# TIPD156_SCH.net
KiCad netlist of a schematic drawn in Altium Designer
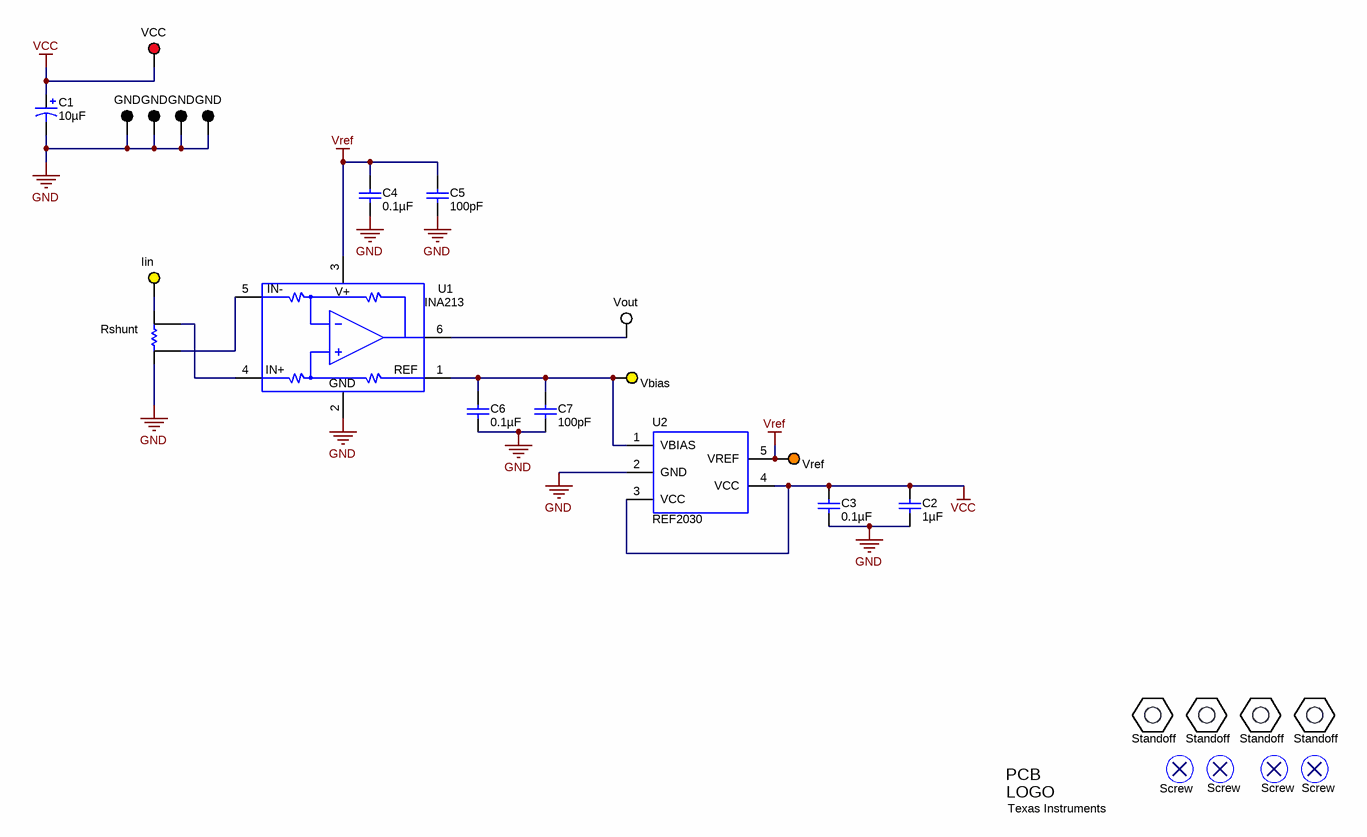
[diagram p0: TIPD156 SCH.SchDoc]

(export (version "E")
  (design (tool "Eeschema 10.0.6"))
  (components
    (comp (ref "C1")
      (value "TPSC106K025R0500")
      (footprint "6032-28")
      (description "CAP, TA, 10uF, 25V, +/-10%, 0.5 ohm, SMD")
      (fields
        (field (name "VALUEDISPLAYED") "10µF")
        (field (name "MANUFACTURER") "AVX")
        (field (name "PUBLISHER") "Texas Instruments")
      )
      (libsource (lib "Capacitor_Tantalum") (part "TPSC106K025R0500"))
    )
    (comp (ref "C2")
      (value "C1608X7R1C105K")
      (footprint "0603")
      (description "CAP, CERM, 1uF, 16V, +/-10%, X7R, 0603")
      (fields
        (field (name "VALUEDISPLAYED") "1µF")
        (field (name "MANUFACTURER") "TDK")
        (field (name "PUBLISHER") "Texas Instruments")
      )
      (libsource (lib "Capacitor_Ceramic") (part "C1608X7R1C105K"))
    )
    (comp (ref "C3")
      (value "06033C104KAT2A")
      (footprint "0603")
      (description "CAP, CERM, 0.1uF, 25V, +/-10%, X7R, 0603")
      (fields
        (field (name "VALUEDISPLAYED") "0.1µF")
        (field (name "MANUFACTURER") "AVX")
        (field (name "PUBLISHER") "Texas Instruments")
      )
      (libsource (lib "Capacitor_Ceramic") (part "06033C104KAT2A"))
    )
    (comp (ref "C4")
      (value "06033C104KAT2A")
      (footprint "0603")
      (description "CAP, CERM, 0.1uF, 25V, +/-10%, X7R, 0603")
      (fields
        (field (name "VALUEDISPLAYED") "0.1µF")
        (field (name "MANUFACTURER") "AVX")
        (field (name "PUBLISHER") "Texas Instruments")
      )
      (libsource (lib "Capacitor_Ceramic") (part "06033C104KAT2A"))
    )
    (comp (ref "C5")
      (value "06035A101JAT2A")
      (footprint "0603")
      (description "CAP, CERM, 100pF, 50V, +/-5%, C0G/NP0, 0603")
      (fields
        (field (name "VALUEDISPLAYED") "100pF")
        (field (name "MANUFACTURER") "AVX")
        (field (name "PUBLISHER") "Texas Instruments")
      )
      (libsource (lib "Capacitor_Ceramic") (part "06035A101JAT2A"))
    )
    (comp (ref "C6")
      (value "06033C104KAT2A")
      (footprint "0603")
      (description "CAP, CERM, 0.1uF, 25V, +/-10%, X7R, 0603")
      (fields
        (field (name "VALUEDISPLAYED") "0.1µF")
        (field (name "MANUFACTURER") "AVX")
        (field (name "PUBLISHER") "Texas Instruments")
      )
      (libsource (lib "Capacitor_Ceramic") (part "06033C104KAT2A"))
    )
    (comp (ref "C7")
      (value "06035A101JAT2A")
      (footprint "0603")
      (description "CAP, CERM, 100pF, 50V, +/-5%, C0G/NP0, 0603")
      (fields
        (field (name "VALUEDISPLAYED") "100pF")
        (field (name "MANUFACTURER") "AVX")
        (field (name "PUBLISHER") "Texas Instruments")
      )
      (libsource (lib "Capacitor_Ceramic") (part "06035A101JAT2A"))
    )
    (comp (ref "Logo1")
      (value "Texas Instruments")
      (footprint "TI_Symbol_Overlay_Small")
      (description "Texas Instrument Corporate Signature")
      (fields (field (name "SYMBOLCREATOR") "codlsc") (field (name "PUBLISHER") "Texas Instruments"))
      (libsource (lib "Logos") (part "TI_Logo"))
    )
    (comp (ref "Rshunt")
      (value "~")
      (footprint "myPCBlib:CSM2512")
      (description "RES, 0.010 ohm, 0.1%, 1W, CSM2512")
      (fields (field (name "PUBLISHER") "Texas Instruments"))
      (libsource (lib "mySCHlib") (part "10m ohm shunt resistor"))
    )
    (comp (ref "TP1")
      (value "Vout")
      (footprint "Keystone5007")
      (description "Test Point, Compact, White, TH")
      (fields
        (field (name "PARTNUMBER") "5007")
        (field (name "MANUFACTURER") "Keystone")
        (field (name "PUBLISHER") "Texas Instruments")
      )
      (libsource (lib "Connectors") (part "5007"))
    )
    (comp (ref "TP2")
      (value "VCC")
      (footprint "Keystone5005")
      (description "Test Point, TH, Compact, Red")
      (fields
        (field (name "MANUFACTURER") "Keystone")
        (field (name "DIGIKEYPARTNUMBER") "5005K-ND")
        (field (name "PUBLISHER") "Texas Instruments")
      )
      (libsource (lib "TemplateSCHLib") (part "5005"))
    )
    (comp (ref "TP3")
      (value "GND")
      (footprint "Keystone5006")
      (description "Test Point, TH, Compact, Black")
      (fields
        (field (name "MANUFACTURER") "Keystone")
        (field (name "DIGIKEYPARTNUMBER") "5006K-ND")
        (field (name "PUBLISHER") "Texas Instruments")
      )
      (libsource (lib "TemplateSCHLib") (part "5006"))
    )
    (comp (ref "TP4")
      (value "GND")
      (footprint "Keystone5006")
      (description "Test Point, TH, Compact, Black")
      (fields
        (field (name "MANUFACTURER") "Keystone")
        (field (name "DIGIKEYPARTNUMBER") "5006K-ND")
        (field (name "PUBLISHER") "Texas Instruments")
      )
      (libsource (lib "TemplateSCHLib") (part "5006"))
    )
    (comp (ref "TP5")
      (value "GND")
      (footprint "Keystone5006")
      (description "Test Point, TH, Compact, Black")
      (fields
        (field (name "MANUFACTURER") "Keystone")
        (field (name "DIGIKEYPARTNUMBER") "5006K-ND")
        (field (name "PUBLISHER") "Texas Instruments")
      )
      (libsource (lib "TemplateSCHLib") (part "5006"))
    )
    (comp (ref "TP6")
      (value "GND")
      (footprint "Keystone5006")
      (description "Test Point, TH, Compact, Black")
      (fields
        (field (name "MANUFACTURER") "Keystone")
        (field (name "DIGIKEYPARTNUMBER") "5006K-ND")
        (field (name "PUBLISHER") "Texas Instruments")
      )
      (libsource (lib "TemplateSCHLib") (part "5006"))
    )
    (comp (ref "TP7")
      (value "Vbias")
      (footprint "Keystone5009")
      (description "Test Point, Compact, Yellow, TH")
      (fields
        (field (name "PARTNUMBER") "5009")
        (field (name "MANUFACTURER") "Keystone")
        (field (name "PUBLISHER") "Texas Instruments")
      )
      (libsource (lib "Connectors") (part "5009"))
    )
    (comp (ref "TP8")
      (value "Vref")
      (footprint "Keystone5008")
      (description "Test Point, Compact, Orange, TH")
      (fields
        (field (name "PARTNUMBER") "5008")
        (field (name "MANUFACTURER") "Keystone")
        (field (name "PUBLISHER") "Texas Instruments")
      )
      (libsource (lib "Connectors") (part "5008"))
    )
    (comp (ref "TP9")
      (value "Iin")
      (footprint "Keystone5009")
      (description "Test Point, Compact, Yellow, TH")
      (fields
        (field (name "PARTNUMBER") "5009")
        (field (name "MANUFACTURER") "Keystone")
        (field (name "PUBLISHER") "Texas Instruments")
      )
      (libsource (lib "Connectors") (part "5009"))
    )
    (comp (ref "U1")
      (value "INA213")
      (footprint "PALinearPCBLib:SC70-6 (DCK) Low Density")
      (description "IC, Low Power, Single-Supply Differrence Amplifier")
      (fields (field (name "PARTNUMBER") "INA132U") (field (name "MANUFACTURER") "TI"))
      (libsource (lib "PALinearSCHLib") (part "INA213"))
    )
    (comp (ref "U2")
      (value "REF2030")
      (footprint "PALinearPCBLib:SOT23-5 (DBV) low density")
      (fields (field (name "MANUFACTURER") "Texas Instruments") (field (name "SYMBOLCREATOR") "Use a-id"))
      (libsource (lib "PALinearSCHLib") (part "REF2030"))
    )
    (comp (ref "U90")
      (value "Standoff")
      (footprint "STANDOFF HEX 4-40THR ALUM 1\"L")
      (description "STANDOFF HEX 4-40THR ALUM 1\"L")
      (fields
        (field (name "MANUFACTURER") "Keystone")
        (field (name "PARTNUMBER") "2205")
        (field (name "SYMBOLCREATOR") "Use LDAP id")
      )
      (libsource (lib "TemplateSCHLib") (part "Standoff, 1{dblquote}, 4-40, Alum, F-F"))
    )
    (comp (ref "U91")
      (value "Standoff")
      (footprint "STANDOFF HEX 4-40THR ALUM 1\"L")
      (description "STANDOFF HEX 4-40THR ALUM 1\"L")
      (fields
        (field (name "MANUFACTURER") "Keystone")
        (field (name "PARTNUMBER") "2205")
        (field (name "SYMBOLCREATOR") "Use LDAP id")
      )
      (libsource (lib "TemplateSCHLib") (part "Standoff, 1{dblquote}, 4-40, Alum, F-F"))
    )
    (comp (ref "U92")
      (value "Standoff")
      (footprint "STANDOFF HEX 4-40THR ALUM 1\"L")
      (description "STANDOFF HEX 4-40THR ALUM 1\"L")
      (fields
        (field (name "MANUFACTURER") "Keystone")
        (field (name "PARTNUMBER") "2205")
        (field (name "SYMBOLCREATOR") "Use LDAP id")
      )
      (libsource (lib "TemplateSCHLib") (part "Standoff, 1{dblquote}, 4-40, Alum, F-F"))
    )
    (comp (ref "U93")
      (value "Standoff")
      (footprint "STANDOFF HEX 4-40THR ALUM 1\"L")
      (description "STANDOFF HEX 4-40THR ALUM 1\"L")
      (fields
        (field (name "MANUFACTURER") "Keystone")
        (field (name "PARTNUMBER") "2205")
        (field (name "SYMBOLCREATOR") "Use LDAP id")
      )
      (libsource (lib "TemplateSCHLib") (part "Standoff, 1{dblquote}, 4-40, Alum, F-F"))
    )
    (comp (ref "U94")
      (value "Screw")
      (description "MACHINE SCREW PAN PHILLIPS 4-40")
      (fields
        (field (name "MANUFACTURER") "B&F Fastener Supply")
        (field (name "PARTNUMBER") "PMSSS 440 0025 PH")
        (field (name "SYMBOLCREATOR") "Use LDAP id")
      )
      (libsource (lib "TemplateSCHLib") (part "Machine Screw, 4-40, 0.25{dblquote}"))
    )
    (comp (ref "U95")
      (value "Screw")
      (description "MACHINE SCREW PAN PHILLIPS 4-40")
      (fields
        (field (name "MANUFACTURER") "B&F Fastener Supply")
        (field (name "PARTNUMBER") "PMSSS 440 0025 PH")
        (field (name "SYMBOLCREATOR") "Use LDAP id")
      )
      (libsource (lib "TemplateSCHLib") (part "Machine Screw, 4-40, 0.25{dblquote}"))
    )
    (comp (ref "U96")
      (value "Screw")
      (description "MACHINE SCREW PAN PHILLIPS 4-40")
      (fields
        (field (name "MANUFACTURER") "B&F Fastener Supply")
        (field (name "PARTNUMBER") "PMSSS 440 0025 PH")
        (field (name "SYMBOLCREATOR") "Use LDAP id")
      )
      (libsource (lib "TemplateSCHLib") (part "Machine Screw, 4-40, 0.25{dblquote}"))
    )
    (comp (ref "U97")
      (value "Screw")
      (description "MACHINE SCREW PAN PHILLIPS 4-40")
      (fields
        (field (name "MANUFACTURER") "B&F Fastener Supply")
        (field (name "PARTNUMBER") "PMSSS 440 0025 PH")
        (field (name "SYMBOLCREATOR") "Use LDAP id")
      )
      (libsource (lib "TemplateSCHLib") (part "Machine Screw, 4-40, 0.25{dblquote}"))
    )
  )
  (nets
    (net (code "1") (name "GND") (class "Default")
      (node (ref "C1") (pin "2") (pinfunction "-_2") (pintype "passive"))
      (node (ref "C2") (pin "2") (pinfunction "2_2") (pintype "passive"))
      (node (ref "C3") (pin "2") (pinfunction "2_2") (pintype "passive"))
      (node (ref "C4") (pin "2") (pinfunction "2_2") (pintype "passive"))
      (node (ref "C5") (pin "2") (pinfunction "2_2") (pintype "passive"))
      (node (ref "C6") (pin "2") (pinfunction "2_2") (pintype "passive"))
      (node (ref "C7") (pin "2") (pinfunction "2_2") (pintype "passive"))
      (node (ref "Rshunt") (pin "I2") (pinfunction "1_I2") (pintype "passive"))
      (node (ref "TP3") (pin "1") (pintype "passive"))
      (node (ref "TP4") (pin "1") (pintype "passive"))
      (node (ref "TP5") (pin "1") (pintype "passive"))
      (node (ref "TP6") (pin "1") (pintype "passive"))
      (node (ref "U1") (pin "2") (pinfunction "GND_2") (pintype "passive"))
      (node (ref "U2") (pin "2") (pinfunction "GND_2") (pintype "passive"))
    )
    (net (code "2") (name "Net-(Rshunt-2)") (class "Default")
      (node (ref "Rshunt") (pin "I1") (pinfunction "2_I1") (pintype "passive"))
      (node (ref "TP9") (pin "1") (pintype "passive"))
    )
    (net (code "3") (name "Net-(Rshunt-3)") (class "Default")
      (node (ref "Rshunt") (pin "E1") (pinfunction "3_E1") (pintype "passive"))
      (node (ref "U1") (pin "4") (pinfunction "3_4") (pintype "passive"))
    )
    (net (code "4") (name "Net-(Rshunt-4)") (class "Default")
      (node (ref "Rshunt") (pin "E2") (pinfunction "4_E2") (pintype "passive"))
      (node (ref "U1") (pin "5") (pinfunction "4_5") (pintype "passive"))
    )
    (net (code "5") (name "Net-(U1-2)") (class "Default")
      (node (ref "C6") (pin "1") (pinfunction "1_1") (pintype "passive"))
      (node (ref "C7") (pin "1") (pinfunction "1_1") (pintype "passive"))
      (node (ref "TP7") (pin "1") (pintype "passive"))
      (node (ref "U1") (pin "1") (pinfunction "2_1") (pintype "passive"))
      (node (ref "U2") (pin "1") (pinfunction "VBIAS_1") (pintype "passive"))
    )
    (net (code "6") (name "Net-(U1-5)") (class "Default")
      (node (ref "TP1") (pin "1") (pintype "passive"))
      (node (ref "U1") (pin "6") (pinfunction "5_6") (pintype "passive"))
    )
    (net (code "7") (name "VCC") (class "Default")
      (node (ref "C1") (pin "1") (pinfunction "+_1") (pintype "passive"))
      (node (ref "C2") (pin "1") (pinfunction "1_1") (pintype "passive"))
      (node (ref "C3") (pin "1") (pinfunction "1_1") (pintype "passive"))
      (node (ref "TP2") (pin "1") (pintype "passive"))
      (node (ref "U2") (pin "3") (pinfunction "VCC_3") (pintype "passive"))
      (node (ref "U2") (pin "4") (pinfunction "VCC_4") (pintype "passive"))
    )
    (net (code "8") (name "Vref") (class "Default")
      (node (ref "C4") (pin "1") (pinfunction "1_1") (pintype "passive"))
      (node (ref "C5") (pin "1") (pinfunction "1_1") (pintype "passive"))
      (node (ref "TP8") (pin "1") (pintype "passive"))
      (node (ref "U1") (pin "3") (pinfunction "V+_3") (pintype "passive"))
      (node (ref "U2") (pin "5") (pinfunction "VREF_5") (pintype "passive"))
    )
  )
)
